# Z-Axis_Stepper_Motor_Driver.net
KiCad netlist of a schematic drawn in Altium Designer
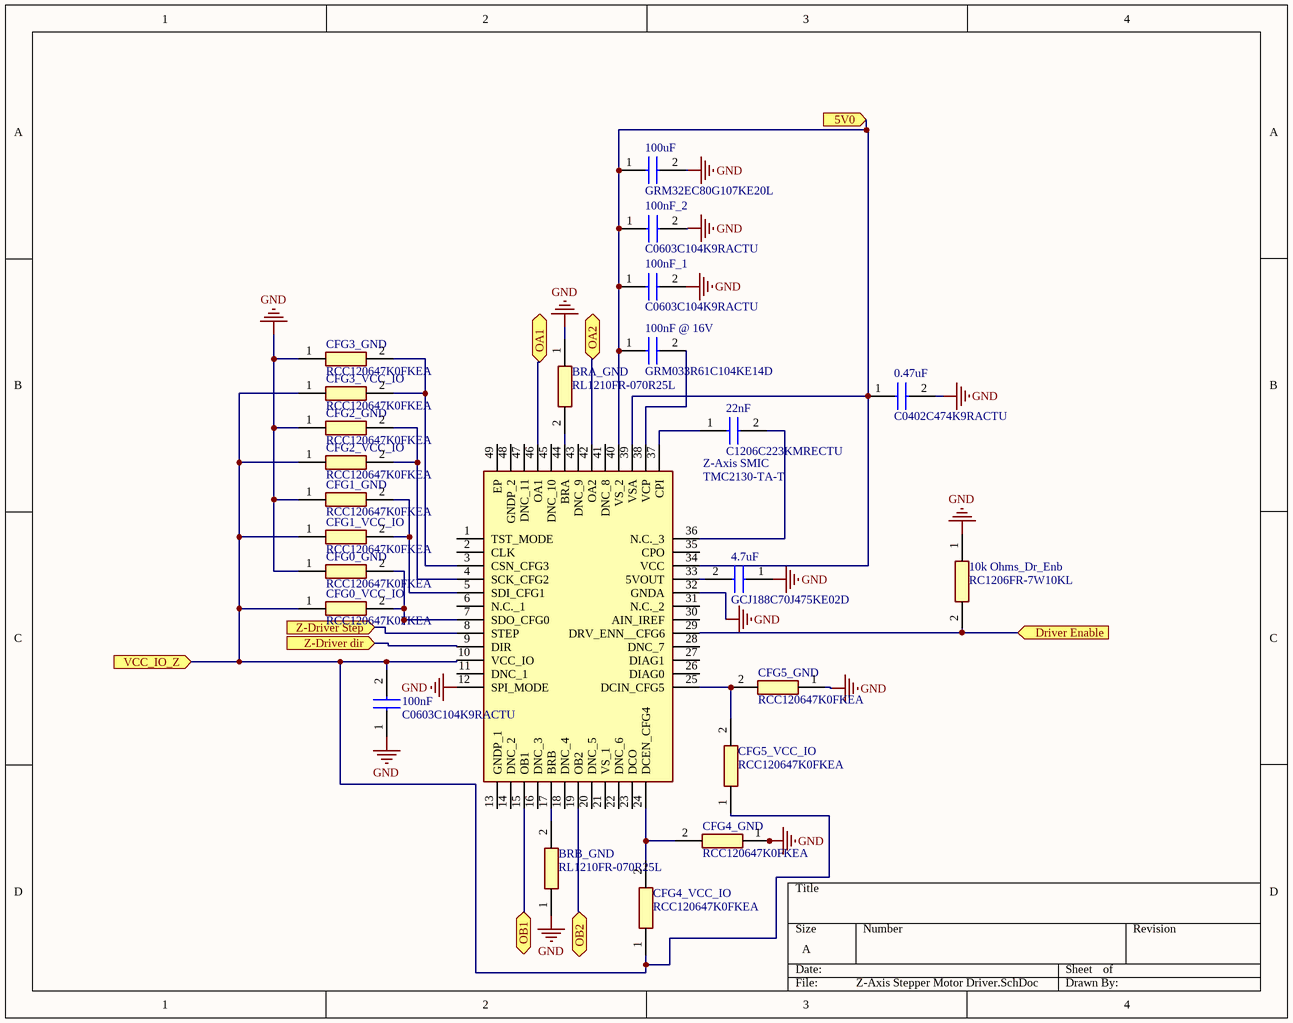
[diagram p0: Z-Axis Stepper Motor Driver.SchDoc]

(export (version "E")
  (design (tool "Eeschema 10.0.6"))
  (components
    (comp (ref "0.47uF")
      (value "C0402C474K9RACTU")
      (footprint "SamacSys:CAPC1005X55N")
      (description "Capacitor")
      (fields (field (name "MOUSER PART NUMBER") "80-C0402C474K9RACTU"))
      (libsource (lib "*") (part "C0402C474K9RACTU"))
    )
    (comp (ref "4.7uF")
      (value "GCJ188C70J475KE02D")
      (footprint "SamacSys:CAPC1608X100N")
      (description "Capacitor")
      (fields (field (name "MOUSER PART NUMBER") "81-GCJ188C70J475KE2D"))
      (libsource (lib "*") (part "GCJ188C70J475KE02D"))
    )
    (comp (ref "10k Ohms_Dr_Enb")
      (value "RC1206FR-7W10KL")
      (footprint "SamacSys:RESC3116X65N")
      (description "Resistor")
      (libsource (lib "*") (part "RC1206FR-7W10KL"))
    )
    (comp (ref "22nF")
      (value "C1206C223KMRECTU")
      (footprint "SamacSys:C1206")
      (description "Capacitor")
      (fields (field (name "MOUSER PART NUMBER") "80-C1206C223KMRECTU"))
      (libsource (lib "*") (part "C1206C223KMRECTU"))
    )
    (comp (ref "100nF")
      (value "C0603C104K9RACTU")
      (footprint "SamacSys:C0603")
      (description "Capacitor")
      (fields (field (name "MOUSER PART NUMBER") "80-C0603C104K9R"))
      (libsource (lib "*") (part "C0603C104K9RACTU"))
    )
    (comp (ref "100nF @ 16V")
      (value "GRM033R61C104KE14D")
      (footprint "SamacSys:CAPC0603X33N")
      (description "Capacitor")
      (fields (field (name "MOUSER PART NUMBER") "81-GRM033R61C104KE4D"))
      (libsource (lib "*") (part "GRM033R61C104KE14D"))
    )
    (comp (ref "100nF_1")
      (value "C0603C104K9RACTU")
      (footprint "SamacSys:C0603")
      (description "Capacitor")
      (fields (field (name "MOUSER PART NUMBER") "80-C0603C104K9R"))
      (libsource (lib "*") (part "C0603C104K9RACTU"))
    )
    (comp (ref "100nF_2")
      (value "C0603C104K9RACTU")
      (footprint "SamacSys:C0603")
      (description "Capacitor")
      (fields (field (name "MOUSER PART NUMBER") "80-C0603C104K9R"))
      (libsource (lib "*") (part "C0603C104K9RACTU"))
    )
    (comp (ref "100uF")
      (value "GRM32EC80G107KE20L")
      (footprint "SamacSys:CAPC3225X270N")
      (description "Capacitor")
      (fields (field (name "MOUSER PART NUMBER") "81-GRM32EC80G107KE0L"))
      (libsource (lib "*") (part "GRM32EC80G107KE20L"))
    )
    (comp (ref "BRA_GND")
      (value "RL1210FR-070R25L")
      (footprint "SamacSys:RESC3126X65N")
      (description "Resistor")
      (fields (field (name "MOUSER PART NUMBER") "603-RL1210FR-070R25L"))
      (libsource (lib "") (part "RL1210FR-070R25L_1"))
    )
    (comp (ref "BRB_GND")
      (value "RL1210FR-070R25L")
      (footprint "SamacSys:RESC3126X65N")
      (description "Resistor")
      (fields (field (name "MOUSER PART NUMBER") "603-RL1210FR-070R25L"))
      (libsource (lib "*") (part "RL1210FR-070R25L"))
    )
    (comp (ref "CFG0_GND")
      (value "RCC120647K0FKEA")
      (footprint "SamacSys:RCC1206_e3")
      (description "Resistor")
      (fields (field (name "MOUSER PART NUMBER") "71-RCC120647K0FKEA"))
      (libsource (lib "*") (part "RCC120647K0FKEA"))
    )
    (comp (ref "CFG0_VCC_IO")
      (value "RCC120647K0FKEA")
      (footprint "SamacSys:RCC1206_e3")
      (description "Resistor")
      (fields (field (name "MOUSER PART NUMBER") "71-RCC120647K0FKEA"))
      (libsource (lib "*") (part "RCC120647K0FKEA"))
    )
    (comp (ref "CFG1_GND")
      (value "RCC120647K0FKEA")
      (footprint "SamacSys:RCC1206_e3")
      (description "Resistor")
      (fields (field (name "MOUSER PART NUMBER") "71-RCC120647K0FKEA"))
      (libsource (lib "*") (part "RCC120647K0FKEA"))
    )
    (comp (ref "CFG1_VCC_IO")
      (value "RCC120647K0FKEA")
      (footprint "SamacSys:RCC1206_e3")
      (description "Resistor")
      (fields (field (name "MOUSER PART NUMBER") "71-RCC120647K0FKEA"))
      (libsource (lib "*") (part "RCC120647K0FKEA"))
    )
    (comp (ref "CFG2_GND")
      (value "RCC120647K0FKEA")
      (footprint "SamacSys:RCC1206_e3")
      (description "Resistor")
      (fields (field (name "MOUSER PART NUMBER") "71-RCC120647K0FKEA"))
      (libsource (lib "*") (part "RCC120647K0FKEA"))
    )
    (comp (ref "CFG2_VCC_IO")
      (value "RCC120647K0FKEA")
      (footprint "SamacSys:RCC1206_e3")
      (description "Resistor")
      (fields (field (name "MOUSER PART NUMBER") "71-RCC120647K0FKEA"))
      (libsource (lib "*") (part "RCC120647K0FKEA"))
    )
    (comp (ref "CFG3_GND")
      (value "RCC120647K0FKEA")
      (footprint "SamacSys:RCC1206_e3")
      (description "Resistor")
      (fields (field (name "MOUSER PART NUMBER") "71-RCC120647K0FKEA"))
      (libsource (lib "*") (part "RCC120647K0FKEA"))
    )
    (comp (ref "CFG3_VCC_IO")
      (value "RCC120647K0FKEA")
      (footprint "SamacSys:RCC1206_e3")
      (description "Resistor")
      (fields (field (name "MOUSER PART NUMBER") "71-RCC120647K0FKEA"))
      (libsource (lib "*") (part "RCC120647K0FKEA"))
    )
    (comp (ref "CFG4_GND")
      (value "RCC120647K0FKEA")
      (footprint "SamacSys:RCC1206_e3")
      (description "Resistor")
      (fields (field (name "MOUSER PART NUMBER") "71-RCC120647K0FKEA"))
      (libsource (lib "") (part "RCC120647K0FKEA_2"))
    )
    (comp (ref "CFG4_VCC_IO")
      (value "RCC120647K0FKEA")
      (footprint "SamacSys:RCC1206_e3")
      (description "Resistor")
      (fields (field (name "MOUSER PART NUMBER") "71-RCC120647K0FKEA"))
      (libsource (lib "") (part "RCC120647K0FKEA_1"))
    )
    (comp (ref "CFG5_GND")
      (value "RCC120647K0FKEA")
      (footprint "SamacSys:RCC1206_e3")
      (description "Resistor")
      (fields (field (name "MOUSER PART NUMBER") "71-RCC120647K0FKEA"))
      (libsource (lib "") (part "RCC120647K0FKEA_2"))
    )
    (comp (ref "CFG5_VCC_IO")
      (value "RCC120647K0FKEA")
      (footprint "SamacSys:RCC1206_e3")
      (description "Resistor")
      (fields (field (name "MOUSER PART NUMBER") "71-RCC120647K0FKEA"))
      (libsource (lib "") (part "RCC120647K0FKEA_1"))
    )
    (comp (ref "Z-Axis SMIC")
      (value "TMC2130-TA-T")
      (footprint "SamacSys:QFP50P900X900X120-49N")
      (description "Integrated Circuit")
      (fields (field (name "MOUSER PART NUMBER") "700-TMC2130-TA-T"))
      (libsource (lib "*") (part "TMC2130-TA-T"))
    )
  )
  (nets
    (net (code "1") (name "/5V0") (class "Default")
      (node (ref "0.47uF") (pin "1") (pinfunction "1_1") (pintype "passive"))
      (node (ref "100nF @ 16V") (pin "1") (pinfunction "1_1") (pintype "passive"))
      (node (ref "100nF_1") (pin "1") (pinfunction "1_1") (pintype "passive"))
      (node (ref "100nF_2") (pin "1") (pinfunction "1_1") (pintype "passive"))
      (node (ref "100uF") (pin "1") (pinfunction "1_1") (pintype "passive"))
      (node (ref "Z-Axis SMIC") (pin "34") (pinfunction "VCC_34") (pintype "passive"))
      (node (ref "Z-Axis SMIC") (pin "39") (pinfunction "VSA_39") (pintype "passive"))
      (node (ref "Z-Axis SMIC") (pin "40") (pinfunction "VS_2_40") (pintype "passive"))
    )
    (net (code "2") (name "/Driver Enable") (class "Default")
      (node (ref "10k Ohms_Dr_Enb") (pin "2") (pinfunction "2_2") (pintype "passive"))
      (node (ref "Z-Axis SMIC") (pin "29") (pinfunction "DRV_ENN__CFG6_29") (pintype "passive"))
    )
    (net (code "3") (name "/OA1") (class "Default")
      (node (ref "Z-Axis SMIC") (pin "46") (pinfunction "OA1_46") (pintype "passive"))
    )
    (net (code "4") (name "/OA2") (class "Default")
      (node (ref "Z-Axis SMIC") (pin "42") (pinfunction "OA2_42") (pintype "passive"))
    )
    (net (code "5") (name "/OB1") (class "Default")
      (node (ref "Z-Axis SMIC") (pin "15") (pinfunction "OB1_15") (pintype "passive"))
    )
    (net (code "6") (name "/OB2") (class "Default")
      (node (ref "Z-Axis SMIC") (pin "19") (pinfunction "OB2_19") (pintype "passive"))
    )
    (net (code "7") (name "/VCC_IO_Z") (class "Default")
      (node (ref "100nF") (pin "2") (pinfunction "2_2") (pintype "passive"))
      (node (ref "CFG0_VCC_IO") (pin "1") (pinfunction "1_1") (pintype "passive"))
      (node (ref "CFG1_VCC_IO") (pin "1") (pinfunction "1_1") (pintype "passive"))
      (node (ref "CFG2_VCC_IO") (pin "1") (pinfunction "1_1") (pintype "passive"))
      (node (ref "CFG3_VCC_IO") (pin "1") (pinfunction "1_1") (pintype "passive"))
      (node (ref "CFG4_VCC_IO") (pin "1") (pinfunction "1_1") (pintype "passive"))
      (node (ref "CFG5_VCC_IO") (pin "1") (pinfunction "1_1") (pintype "passive"))
      (node (ref "Z-Axis SMIC") (pin "10") (pinfunction "VCC_IO_10") (pintype "passive"))
    )
    (net (code "8") (name "/Z-Driver Step") (class "Default")
      (node (ref "Z-Axis SMIC") (pin "8") (pinfunction "STEP_8") (pintype "passive"))
    )
    (net (code "9") (name "/Z-Driver dir") (class "Default")
      (node (ref "Z-Axis SMIC") (pin "9") (pinfunction "DIR_9") (pintype "passive"))
    )
    (net (code "10") (name "GND") (class "Default")
      (node (ref "0.47uF") (pin "2") (pinfunction "2_2") (pintype "passive"))
      (node (ref "100nF") (pin "1") (pinfunction "1_1") (pintype "passive"))
      (node (ref "100nF_1") (pin "2") (pinfunction "2_2") (pintype "passive"))
      (node (ref "100nF_2") (pin "2") (pinfunction "2_2") (pintype "passive"))
      (node (ref "100uF") (pin "2") (pinfunction "2_2") (pintype "passive"))
      (node (ref "10k Ohms_Dr_Enb") (pin "1") (pinfunction "1_1") (pintype "passive"))
      (node (ref "4.7uF") (pin "1") (pinfunction "1_1") (pintype "passive"))
      (node (ref "BRA_GND") (pin "1") (pinfunction "1_1") (pintype "passive"))
      (node (ref "BRB_GND") (pin "1") (pinfunction "1_1") (pintype "passive"))
      (node (ref "CFG0_GND") (pin "1") (pinfunction "1_1") (pintype "passive"))
      (node (ref "CFG1_GND") (pin "1") (pinfunction "1_1") (pintype "passive"))
      (node (ref "CFG2_GND") (pin "1") (pinfunction "1_1") (pintype "passive"))
      (node (ref "CFG3_GND") (pin "1") (pinfunction "1_1") (pintype "passive"))
      (node (ref "CFG4_GND") (pin "1") (pinfunction "1_1") (pintype "passive"))
      (node (ref "CFG5_GND") (pin "1") (pinfunction "1_1") (pintype "passive"))
      (node (ref "Z-Axis SMIC") (pin "12") (pinfunction "SPI_MODE_12") (pintype "passive"))
      (node (ref "Z-Axis SMIC") (pin "32") (pinfunction "GNDA_32") (pintype "passive"))
    )
    (net (code "11") (name "Net-(Z-Axis SMIC-5VOUT)") (class "Default")
      (node (ref "4.7uF") (pin "2") (pinfunction "2_2") (pintype "passive"))
      (node (ref "Z-Axis SMIC") (pin "33") (pinfunction "5VOUT_33") (pintype "passive"))
    )
    (net (code "12") (name "Net-(Z-Axis SMIC-BRA)") (class "Default")
      (node (ref "BRA_GND") (pin "2") (pinfunction "2_2") (pintype "passive"))
      (node (ref "Z-Axis SMIC") (pin "44") (pinfunction "BRA_44") (pintype "passive"))
    )
    (net (code "13") (name "Net-(Z-Axis SMIC-BRB)") (class "Default")
      (node (ref "BRB_GND") (pin "2") (pinfunction "2_2") (pintype "passive"))
      (node (ref "Z-Axis SMIC") (pin "17") (pinfunction "BRB_17") (pintype "passive"))
    )
    (net (code "14") (name "Net-(Z-Axis SMIC-CPI)") (class "Default")
      (node (ref "22nF") (pin "1") (pinfunction "1_1") (pintype "passive"))
      (node (ref "Z-Axis SMIC") (pin "37") (pinfunction "CPI_37") (pintype "passive"))
    )
    (net (code "15") (name "Net-(Z-Axis SMIC-CSN_CFG3)") (class "Default")
      (node (ref "CFG3_GND") (pin "2") (pinfunction "2_2") (pintype "passive"))
      (node (ref "CFG3_VCC_IO") (pin "2") (pinfunction "2_2") (pintype "passive"))
      (node (ref "Z-Axis SMIC") (pin "3") (pinfunction "CSN_CFG3_3") (pintype "passive"))
    )
    (net (code "16") (name "Net-(Z-Axis SMIC-DCEN_CFG4)") (class "Default")
      (node (ref "CFG4_GND") (pin "2") (pinfunction "2_2") (pintype "passive"))
      (node (ref "CFG4_VCC_IO") (pin "2") (pinfunction "2_2") (pintype "passive"))
      (node (ref "Z-Axis SMIC") (pin "24") (pinfunction "DCEN_CFG4_24") (pintype "passive"))
    )
    (net (code "17") (name "Net-(Z-Axis SMIC-DCIN_CFG5)") (class "Default")
      (node (ref "CFG5_GND") (pin "2") (pinfunction "2_2") (pintype "passive"))
      (node (ref "CFG5_VCC_IO") (pin "2") (pinfunction "2_2") (pintype "passive"))
      (node (ref "Z-Axis SMIC") (pin "25") (pinfunction "DCIN_CFG5_25") (pintype "passive"))
    )
    (net (code "18") (name "Net-(Z-Axis SMIC-N.C._3)") (class "Default")
      (node (ref "22nF") (pin "2") (pinfunction "2_2") (pintype "passive"))
      (node (ref "Z-Axis SMIC") (pin "36") (pinfunction "N.C._3_36") (pintype "passive"))
    )
    (net (code "19") (name "Net-(Z-Axis SMIC-SCK_CFG2)") (class "Default")
      (node (ref "CFG2_GND") (pin "2") (pinfunction "2_2") (pintype "passive"))
      (node (ref "CFG2_VCC_IO") (pin "2") (pinfunction "2_2") (pintype "passive"))
      (node (ref "Z-Axis SMIC") (pin "4") (pinfunction "SCK_CFG2_4") (pintype "passive"))
    )
    (net (code "20") (name "Net-(Z-Axis SMIC-SDI_CFG1)") (class "Default")
      (node (ref "CFG1_GND") (pin "2") (pinfunction "2_2") (pintype "passive"))
      (node (ref "CFG1_VCC_IO") (pin "2") (pinfunction "2_2") (pintype "passive"))
      (node (ref "Z-Axis SMIC") (pin "5") (pinfunction "SDI_CFG1_5") (pintype "passive"))
    )
    (net (code "21") (name "Net-(Z-Axis SMIC-SDO_CFG0)") (class "Default")
      (node (ref "CFG0_GND") (pin "2") (pinfunction "2_2") (pintype "passive"))
      (node (ref "CFG0_VCC_IO") (pin "2") (pinfunction "2_2") (pintype "passive"))
      (node (ref "Z-Axis SMIC") (pin "7") (pinfunction "SDO_CFG0_7") (pintype "passive"))
    )
    (net (code "22") (name "Net-(Z-Axis SMIC-VCP)") (class "Default")
      (node (ref "100nF @ 16V") (pin "2") (pinfunction "2_2") (pintype "passive"))
      (node (ref "Z-Axis SMIC") (pin "38") (pinfunction "VCP_38") (pintype "passive"))
    )
    (net (code "23") (name "unconnected-(Z-Axis SMIC-AIN_IREF-Pad30)") (class "Default")
      (node (ref "Z-Axis SMIC") (pin "30") (pinfunction "AIN_IREF_30") (pintype "passive"))
    )
    (net (code "24") (name "unconnected-(Z-Axis SMIC-CLK-Pad2)") (class "Default")
      (node (ref "Z-Axis SMIC") (pin "2") (pinfunction "CLK_2") (pintype "passive"))
    )
    (net (code "25") (name "unconnected-(Z-Axis SMIC-CPO-Pad35)") (class "Default")
      (node (ref "Z-Axis SMIC") (pin "35") (pinfunction "CPO_35") (pintype "passive"))
    )
    (net (code "26") (name "unconnected-(Z-Axis SMIC-DCO-Pad23)") (class "Default")
      (node (ref "Z-Axis SMIC") (pin "23") (pinfunction "DCO_23") (pintype "passive"))
    )
    (net (code "27") (name "unconnected-(Z-Axis SMIC-DIAG0-Pad26)") (class "Default")
      (node (ref "Z-Axis SMIC") (pin "26") (pinfunction "DIAG0_26") (pintype "passive"))
    )
    (net (code "28") (name "unconnected-(Z-Axis SMIC-DIAG1-Pad27)") (class "Default")
      (node (ref "Z-Axis SMIC") (pin "27") (pinfunction "DIAG1_27") (pintype "passive"))
    )
    (net (code "29") (name "unconnected-(Z-Axis SMIC-DNC_1-Pad11)") (class "Default")
      (node (ref "Z-Axis SMIC") (pin "11") (pinfunction "DNC_1_11") (pintype "passive"))
    )
    (net (code "30") (name "unconnected-(Z-Axis SMIC-DNC_2-Pad14)") (class "Default")
      (node (ref "Z-Axis SMIC") (pin "14") (pinfunction "DNC_2_14") (pintype "passive"))
    )
    (net (code "31") (name "unconnected-(Z-Axis SMIC-DNC_3-Pad16)") (class "Default")
      (node (ref "Z-Axis SMIC") (pin "16") (pinfunction "DNC_3_16") (pintype "passive"))
    )
    (net (code "32") (name "unconnected-(Z-Axis SMIC-DNC_4-Pad18)") (class "Default")
      (node (ref "Z-Axis SMIC") (pin "18") (pinfunction "DNC_4_18") (pintype "passive"))
    )
    (net (code "33") (name "unconnected-(Z-Axis SMIC-DNC_5-Pad20)") (class "Default")
      (node (ref "Z-Axis SMIC") (pin "20") (pinfunction "DNC_5_20") (pintype "passive"))
    )
    (net (code "34") (name "unconnected-(Z-Axis SMIC-DNC_6-Pad22)") (class "Default")
      (node (ref "Z-Axis SMIC") (pin "22") (pinfunction "DNC_6_22") (pintype "passive"))
    )
    (net (code "35") (name "unconnected-(Z-Axis SMIC-DNC_7-Pad28)") (class "Default")
      (node (ref "Z-Axis SMIC") (pin "28") (pinfunction "DNC_7_28") (pintype "passive"))
    )
    (net (code "36") (name "unconnected-(Z-Axis SMIC-DNC_8-Pad41)") (class "Default")
      (node (ref "Z-Axis SMIC") (pin "41") (pinfunction "DNC_8_41") (pintype "passive"))
    )
    (net (code "37") (name "unconnected-(Z-Axis SMIC-DNC_9-Pad43)") (class "Default")
      (node (ref "Z-Axis SMIC") (pin "43") (pinfunction "DNC_9_43") (pintype "passive"))
    )
    (net (code "38") (name "unconnected-(Z-Axis SMIC-DNC_10-Pad45)") (class "Default")
      (node (ref "Z-Axis SMIC") (pin "45") (pinfunction "DNC_10_45") (pintype "passive"))
    )
    (net (code "39") (name "unconnected-(Z-Axis SMIC-DNC_11-Pad47)") (class "Default")
      (node (ref "Z-Axis SMIC") (pin "47") (pinfunction "DNC_11_47") (pintype "passive"))
    )
    (net (code "40") (name "unconnected-(Z-Axis SMIC-EP-Pad49)") (class "Default")
      (node (ref "Z-Axis SMIC") (pin "49") (pinfunction "EP_49") (pintype "passive"))
    )
    (net (code "41") (name "unconnected-(Z-Axis SMIC-GNDP_1-Pad13)") (class "Default")
      (node (ref "Z-Axis SMIC") (pin "13") (pinfunction "GNDP_1_13") (pintype "passive"))
    )
    (net (code "42") (name "unconnected-(Z-Axis SMIC-GNDP_2-Pad48)") (class "Default")
      (node (ref "Z-Axis SMIC") (pin "48") (pinfunction "GNDP_2_48") (pintype "passive"))
    )
    (net (code "43") (name "unconnected-(Z-Axis SMIC-N.C._1-Pad6)") (class "Default")
      (node (ref "Z-Axis SMIC") (pin "6") (pinfunction "N.C._1_6") (pintype "passive"))
    )
    (net (code "44") (name "unconnected-(Z-Axis SMIC-N.C._2-Pad31)") (class "Default")
      (node (ref "Z-Axis SMIC") (pin "31") (pinfunction "N.C._2_31") (pintype "passive"))
    )
    (net (code "45") (name "unconnected-(Z-Axis SMIC-TST_MODE-Pad1)") (class "Default")
      (node (ref "Z-Axis SMIC") (pin "1") (pinfunction "TST_MODE_1") (pintype "passive"))
    )
    (net (code "46") (name "unconnected-(Z-Axis SMIC-VS_1-Pad21)") (class "Default")
      (node (ref "Z-Axis SMIC") (pin "21") (pinfunction "VS_1_21") (pintype "passive"))
    )
  )
)
